# VC_Panning_Mixer_main.net
KiCad netlist of a schematic drawn in EAGLE
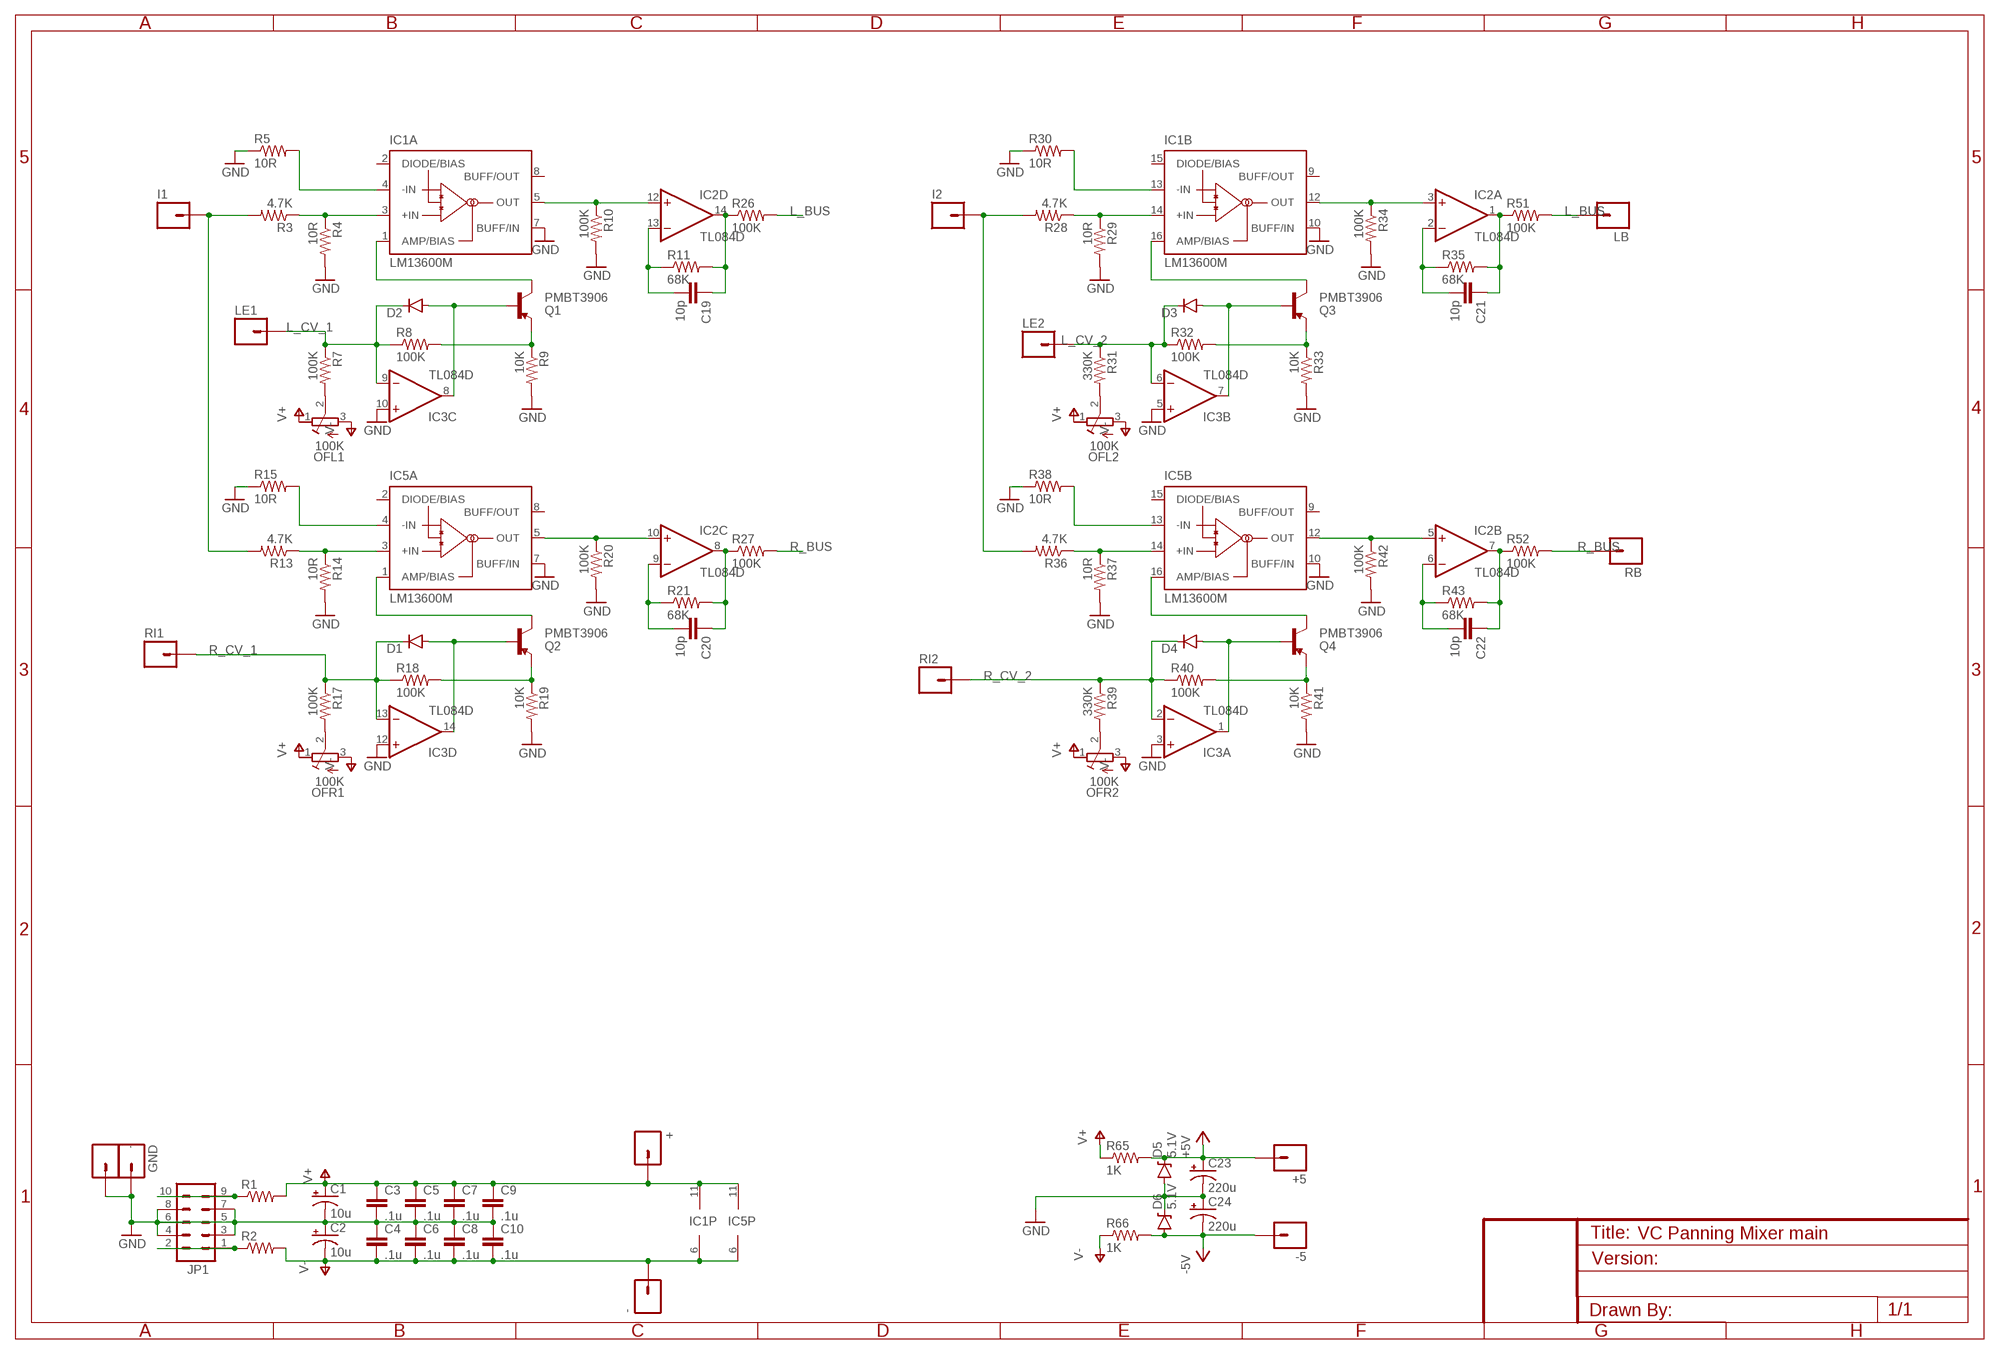
[diagram p0: schematic, sheet 1]

(export (version "E")
  (design (tool "Eeschema 10.0.6"))
  (components
    (comp (ref "+")
      (value "M01PTH")
      (footprint "eagle-import:1X01")
      (libsource (lib "eagle-import") (part "M01PTH"))
    )
    (comp (ref "+5")
      (value "M01PTH")
      (footprint "eagle-import:1X01")
      (libsource (lib "eagle-import") (part "M01PTH"))
    )
    (comp (ref "-")
      (value "M01PTH")
      (footprint "eagle-import:1X01")
      (libsource (lib "eagle-import") (part "M01PTH"))
    )
    (comp (ref "-5")
      (value "M01PTH")
      (footprint "eagle-import:1X01")
      (libsource (lib "eagle-import") (part "M01PTH"))
    )
    (comp (ref ".")
      (value "M01PTH")
      (footprint "eagle-import:1X01")
      (libsource (lib "eagle-import") (part "M01PTH"))
    )
    (comp (ref "C1")
      (value "10u")
      (footprint "eagle-import:CPOL-RADIAL-10UF-25V")
      (libsource (lib "eagle-import") (part "CAP_POLPTH2"))
    )
    (comp (ref "C2")
      (value "10u")
      (footprint "eagle-import:CPOL-RADIAL-10UF-25V")
      (libsource (lib "eagle-import") (part "CAP_POLPTH2"))
    )
    (comp (ref "C3")
      (value ".1u")
      (footprint "eagle-import:0805")
      (libsource (lib "eagle-import") (part "CAP0805"))
    )
    (comp (ref "C4")
      (value ".1u")
      (footprint "eagle-import:0805")
      (libsource (lib "eagle-import") (part "CAP0805"))
    )
    (comp (ref "C5")
      (value ".1u")
      (footprint "eagle-import:0805")
      (libsource (lib "eagle-import") (part "CAP0805"))
    )
    (comp (ref "C6")
      (value ".1u")
      (footprint "eagle-import:0805")
      (libsource (lib "eagle-import") (part "CAP0805"))
    )
    (comp (ref "C7")
      (value ".1u")
      (footprint "eagle-import:0805")
      (libsource (lib "eagle-import") (part "CAP0805"))
    )
    (comp (ref "C8")
      (value ".1u")
      (footprint "eagle-import:0805")
      (libsource (lib "eagle-import") (part "CAP0805"))
    )
    (comp (ref "C9")
      (value ".1u")
      (footprint "eagle-import:0805")
      (libsource (lib "eagle-import") (part "CAP0805"))
    )
    (comp (ref "C10")
      (value ".1u")
      (footprint "eagle-import:0805")
      (libsource (lib "eagle-import") (part "CAP0805"))
    )
    (comp (ref "C19")
      (value "10p")
      (footprint "eagle-import:0805")
      (libsource (lib "eagle-import") (part "CAP0805"))
    )
    (comp (ref "C20")
      (value "10p")
      (footprint "eagle-import:0805")
      (libsource (lib "eagle-import") (part "CAP0805"))
    )
    (comp (ref "C21")
      (value "10p")
      (footprint "eagle-import:0805")
      (libsource (lib "eagle-import") (part "CAP0805"))
    )
    (comp (ref "C22")
      (value "10p")
      (footprint "eagle-import:0805")
      (libsource (lib "eagle-import") (part "CAP0805"))
    )
    (comp (ref "C23")
      (value "220u")
      (footprint "eagle-import:CPOL-RADIAL-10UF-25V")
      (libsource (lib "eagle-import") (part "CAP_POLPTH2"))
    )
    (comp (ref "C24")
      (value "220u")
      (footprint "eagle-import:CPOL-RADIAL-10UF-25V")
      (libsource (lib "eagle-import") (part "CAP_POLPTH2"))
    )
    (comp (ref "D1")
      (value "DIODESOD123")
      (footprint "eagle-import:SOD-123")
      (libsource (lib "eagle-import") (part "DIODESOD123"))
    )
    (comp (ref "D2")
      (value "DIODESOD123")
      (footprint "eagle-import:SOD-123")
      (libsource (lib "eagle-import") (part "DIODESOD123"))
    )
    (comp (ref "D3")
      (value "DIODESOD123")
      (footprint "eagle-import:SOD-123")
      (libsource (lib "eagle-import") (part "DIODESOD123"))
    )
    (comp (ref "D4")
      (value "DIODESOD123")
      (footprint "eagle-import:SOD-123")
      (libsource (lib "eagle-import") (part "DIODESOD123"))
    )
    (comp (ref "D5")
      (value "5.1V")
      (footprint "eagle-import:SOD-123")
      (libsource (lib "eagle-import") (part "DIODE-ZENER16V"))
    )
    (comp (ref "D6")
      (value "5.1V")
      (footprint "eagle-import:SOD-123")
      (libsource (lib "eagle-import") (part "DIODE-ZENER16V"))
    )
    (comp (ref "GND")
      (value "M01PTH")
      (footprint "eagle-import:1X01")
      (libsource (lib "eagle-import") (part "M01PTH"))
    )
    (comp (ref "I1")
      (value "M01PTH")
      (footprint "eagle-import:1X01")
      (libsource (lib "eagle-import") (part "M01PTH"))
    )
    (comp (ref "I2")
      (value "M01PTH")
      (footprint "eagle-import:1X01")
      (libsource (lib "eagle-import") (part "M01PTH"))
    )
    (comp (ref "IC1")
      (value "LM13600M")
      (footprint "eagle-import:SO16")
      (libsource (lib "eagle-import") (part "LM13600M"))
    )
    (comp (ref "IC2")
      (value "TL084D")
      (footprint "eagle-import:SO14")
      (libsource (lib "eagle-import") (part "TL084D"))
    )
    (comp (ref "IC3")
      (value "TL084D")
      (footprint "eagle-import:SO14")
      (libsource (lib "eagle-import") (part "TL084D"))
    )
    (comp (ref "IC5")
      (value "LM13600M")
      (footprint "eagle-import:SO16")
      (libsource (lib "eagle-import") (part "LM13600M"))
    )
    (comp (ref "JP1")
      (value "M05X2PTH")
      (footprint "eagle-import:AVR_ICSP")
      (libsource (lib "eagle-import") (part "M05X2PTH"))
    )
    (comp (ref "LB")
      (value "M01PTH")
      (footprint "eagle-import:1X01")
      (libsource (lib "eagle-import") (part "M01PTH"))
    )
    (comp (ref "LE1")
      (value "M01PTH")
      (footprint "eagle-import:1X01")
      (libsource (lib "eagle-import") (part "M01PTH"))
    )
    (comp (ref "LE2")
      (value "M01PTH")
      (footprint "eagle-import:1X01")
      (libsource (lib "eagle-import") (part "M01PTH"))
    )
    (comp (ref "OFL1")
      (value "100K")
      (footprint "eagle-import:RTRIM3314G")
      (libsource (lib "eagle-import") (part "R-TRIMM3314G"))
    )
    (comp (ref "OFL2")
      (value "100K")
      (footprint "eagle-import:RTRIM3314G")
      (libsource (lib "eagle-import") (part "R-TRIMM3314G"))
    )
    (comp (ref "OFR1")
      (value "100K")
      (footprint "eagle-import:RTRIM3314G")
      (libsource (lib "eagle-import") (part "R-TRIMM3314G"))
    )
    (comp (ref "OFR2")
      (value "100K")
      (footprint "eagle-import:RTRIM3314G")
      (libsource (lib "eagle-import") (part "R-TRIMM3314G"))
    )
    (comp (ref "Q1")
      (value "PMBT3906")
      (footprint "eagle-import:SOT23-3")
      (libsource (lib "eagle-import") (part "TRANSISTOR_PNPPMBT3906"))
    )
    (comp (ref "Q2")
      (value "PMBT3906")
      (footprint "eagle-import:SOT23-3")
      (libsource (lib "eagle-import") (part "TRANSISTOR_PNPPMBT3906"))
    )
    (comp (ref "Q3")
      (value "PMBT3906")
      (footprint "eagle-import:SOT23-3")
      (libsource (lib "eagle-import") (part "TRANSISTOR_PNPPMBT3906"))
    )
    (comp (ref "Q4")
      (value "PMBT3906")
      (footprint "eagle-import:SOT23-3")
      (libsource (lib "eagle-import") (part "TRANSISTOR_PNPPMBT3906"))
    )
    (comp (ref "R1")
      (value "RESISTOR0805-RES")
      (footprint "eagle-import:0805@1")
      (libsource (lib "eagle-import") (part "RESISTOR0805-RES"))
    )
    (comp (ref "R2")
      (value "RESISTOR0805-RES")
      (footprint "eagle-import:0805@1")
      (libsource (lib "eagle-import") (part "RESISTOR0805-RES"))
    )
    (comp (ref "R3")
      (value "4.7K")
      (footprint "eagle-import:0805")
      (libsource (lib "eagle-import") (part "SparkFun-Resistors_RESISTOR0805-RES"))
    )
    (comp (ref "R4")
      (value "10R")
      (footprint "eagle-import:0805")
      (libsource (lib "eagle-import") (part "SparkFun-Resistors_RESISTOR0805-RES"))
    )
    (comp (ref "R5")
      (value "10R")
      (footprint "eagle-import:0805")
      (libsource (lib "eagle-import") (part "SparkFun-Resistors_RESISTOR0805-RES"))
    )
    (comp (ref "R7")
      (value "100K")
      (footprint "eagle-import:0805")
      (libsource (lib "eagle-import") (part "SparkFun-Resistors_RESISTOR0805-RES"))
    )
    (comp (ref "R8")
      (value "100K")
      (footprint "eagle-import:0805")
      (libsource (lib "eagle-import") (part "SparkFun-Resistors_RESISTOR0805-RES"))
    )
    (comp (ref "R9")
      (value "10K")
      (footprint "eagle-import:0805")
      (libsource (lib "eagle-import") (part "SparkFun-Resistors_RESISTOR0805-RES"))
    )
    (comp (ref "R10")
      (value "100K")
      (footprint "eagle-import:0805")
      (libsource (lib "eagle-import") (part "SparkFun-Resistors_RESISTOR0805-RES"))
    )
    (comp (ref "R11")
      (value "68K")
      (footprint "eagle-import:0805")
      (libsource (lib "eagle-import") (part "SparkFun-Resistors_RESISTOR0805-RES"))
    )
    (comp (ref "R13")
      (value "4.7K")
      (footprint "eagle-import:0805")
      (libsource (lib "eagle-import") (part "SparkFun-Resistors_RESISTOR0805-RES"))
    )
    (comp (ref "R14")
      (value "10R")
      (footprint "eagle-import:0805")
      (libsource (lib "eagle-import") (part "SparkFun-Resistors_RESISTOR0805-RES"))
    )
    (comp (ref "R15")
      (value "10R")
      (footprint "eagle-import:0805")
      (libsource (lib "eagle-import") (part "SparkFun-Resistors_RESISTOR0805-RES"))
    )
    (comp (ref "R17")
      (value "100K")
      (footprint "eagle-import:0805")
      (libsource (lib "eagle-import") (part "SparkFun-Resistors_RESISTOR0805-RES"))
    )
    (comp (ref "R18")
      (value "100K")
      (footprint "eagle-import:0805")
      (libsource (lib "eagle-import") (part "SparkFun-Resistors_RESISTOR0805-RES"))
    )
    (comp (ref "R19")
      (value "10K")
      (footprint "eagle-import:0805")
      (libsource (lib "eagle-import") (part "SparkFun-Resistors_RESISTOR0805-RES"))
    )
    (comp (ref "R20")
      (value "100K")
      (footprint "eagle-import:0805")
      (libsource (lib "eagle-import") (part "SparkFun-Resistors_RESISTOR0805-RES"))
    )
    (comp (ref "R21")
      (value "68K")
      (footprint "eagle-import:0805")
      (libsource (lib "eagle-import") (part "SparkFun-Resistors_RESISTOR0805-RES"))
    )
    (comp (ref "R26")
      (value "100K")
      (footprint "eagle-import:0805")
      (libsource (lib "eagle-import") (part "SparkFun-Resistors_RESISTOR0805-RES"))
    )
    (comp (ref "R27")
      (value "100K")
      (footprint "eagle-import:0805")
      (libsource (lib "eagle-import") (part "SparkFun-Resistors_RESISTOR0805-RES"))
    )
    (comp (ref "R28")
      (value "4.7K")
      (footprint "eagle-import:0805")
      (libsource (lib "eagle-import") (part "SparkFun-Resistors_RESISTOR0805-RES"))
    )
    (comp (ref "R29")
      (value "10R")
      (footprint "eagle-import:0805")
      (libsource (lib "eagle-import") (part "SparkFun-Resistors_RESISTOR0805-RES"))
    )
    (comp (ref "R30")
      (value "10R")
      (footprint "eagle-import:0805")
      (libsource (lib "eagle-import") (part "SparkFun-Resistors_RESISTOR0805-RES"))
    )
    (comp (ref "R31")
      (value "330K")
      (footprint "eagle-import:0805")
      (libsource (lib "eagle-import") (part "SparkFun-Resistors_RESISTOR0805-RES"))
    )
    (comp (ref "R32")
      (value "100K")
      (footprint "eagle-import:0805")
      (libsource (lib "eagle-import") (part "SparkFun-Resistors_RESISTOR0805-RES"))
    )
    (comp (ref "R33")
      (value "10K")
      (footprint "eagle-import:0805")
      (libsource (lib "eagle-import") (part "SparkFun-Resistors_RESISTOR0805-RES"))
    )
    (comp (ref "R34")
      (value "100K")
      (footprint "eagle-import:0805")
      (libsource (lib "eagle-import") (part "SparkFun-Resistors_RESISTOR0805-RES"))
    )
    (comp (ref "R35")
      (value "68K")
      (footprint "eagle-import:0805")
      (libsource (lib "eagle-import") (part "SparkFun-Resistors_RESISTOR0805-RES"))
    )
    (comp (ref "R36")
      (value "4.7K")
      (footprint "eagle-import:0805")
      (libsource (lib "eagle-import") (part "SparkFun-Resistors_RESISTOR0805-RES"))
    )
    (comp (ref "R37")
      (value "10R")
      (footprint "eagle-import:0805")
      (libsource (lib "eagle-import") (part "SparkFun-Resistors_RESISTOR0805-RES"))
    )
    (comp (ref "R38")
      (value "10R")
      (footprint "eagle-import:0805")
      (libsource (lib "eagle-import") (part "SparkFun-Resistors_RESISTOR0805-RES"))
    )
    (comp (ref "R39")
      (value "330K")
      (footprint "eagle-import:0805")
      (libsource (lib "eagle-import") (part "SparkFun-Resistors_RESISTOR0805-RES"))
    )
    (comp (ref "R40")
      (value "100K")
      (footprint "eagle-import:0805")
      (libsource (lib "eagle-import") (part "SparkFun-Resistors_RESISTOR0805-RES"))
    )
    (comp (ref "R41")
      (value "10K")
      (footprint "eagle-import:0805")
      (libsource (lib "eagle-import") (part "SparkFun-Resistors_RESISTOR0805-RES"))
    )
    (comp (ref "R42")
      (value "100K")
      (footprint "eagle-import:0805")
      (libsource (lib "eagle-import") (part "SparkFun-Resistors_RESISTOR0805-RES"))
    )
    (comp (ref "R43")
      (value "68K")
      (footprint "eagle-import:0805")
      (libsource (lib "eagle-import") (part "SparkFun-Resistors_RESISTOR0805-RES"))
    )
    (comp (ref "R51")
      (value "100K")
      (footprint "eagle-import:0805")
      (libsource (lib "eagle-import") (part "SparkFun-Resistors_RESISTOR0805-RES"))
    )
    (comp (ref "R52")
      (value "100K")
      (footprint "eagle-import:0805")
      (libsource (lib "eagle-import") (part "SparkFun-Resistors_RESISTOR0805-RES"))
    )
    (comp (ref "R65")
      (value "1K")
      (footprint "eagle-import:0805")
      (libsource (lib "eagle-import") (part "SparkFun-Resistors_RESISTOR0805-RES"))
    )
    (comp (ref "R66")
      (value "1K")
      (footprint "eagle-import:0805")
      (libsource (lib "eagle-import") (part "SparkFun-Resistors_RESISTOR0805-RES"))
    )
    (comp (ref "RB")
      (value "M01PTH")
      (footprint "eagle-import:1X01")
      (libsource (lib "eagle-import") (part "M01PTH"))
    )
    (comp (ref "RI1")
      (value "M01PTH")
      (footprint "eagle-import:1X01")
      (libsource (lib "eagle-import") (part "M01PTH"))
    )
    (comp (ref "RI2")
      (value "M01PTH")
      (footprint "eagle-import:1X01")
      (libsource (lib "eagle-import") (part "M01PTH"))
    )
  )
  (nets
    (net (code "1") (name "+5V") (class "Default")
      (node (ref "+5") (pin "1") (pinfunction "1_1") (pintype "passive"))
      (node (ref "C23") (pin "1") (pinfunction "+_1") (pintype "passive"))
      (node (ref "D5") (pin "C") (pinfunction "C_C") (pintype "passive"))
      (node (ref "R65") (pin "2") (pinfunction "2_2") (pintype "passive"))
    )
    (net (code "2") (name "-5V") (class "Default")
      (node (ref "-5") (pin "1") (pinfunction "1_1") (pintype "passive"))
      (node (ref "C24") (pin "2") (pinfunction "-_2") (pintype "passive"))
      (node (ref "D6") (pin "A") (pinfunction "A_A") (pintype "passive"))
      (node (ref "R66") (pin "2") (pinfunction "2_2") (pintype "passive"))
    )
    (net (code "3") (name "/L_BUS") (class "Default")
      (node (ref "LB") (pin "1") (pinfunction "1_1") (pintype "passive"))
      (node (ref "R26") (pin "2") (pinfunction "2_2") (pintype "passive"))
      (node (ref "R51") (pin "2") (pinfunction "2_2") (pintype "passive"))
    )
    (net (code "4") (name "/L_CV_1") (class "Default")
      (node (ref "D2") (pin "C") (pinfunction "C_C") (pintype "passive"))
      (node (ref "IC3") (pin "9") (pinfunction "-IN_9") (pintype "input"))
      (node (ref "LE1") (pin "1") (pinfunction "1_1") (pintype "passive"))
      (node (ref "R7") (pin "1") (pinfunction "1_1") (pintype "passive"))
      (node (ref "R8") (pin "1") (pinfunction "1_1") (pintype "passive"))
    )
    (net (code "5") (name "/L_CV_2") (class "Default")
      (node (ref "D3") (pin "C") (pinfunction "C_C") (pintype "passive"))
      (node (ref "IC3") (pin "6") (pinfunction "-IN_6") (pintype "input"))
      (node (ref "LE2") (pin "1") (pinfunction "1_1") (pintype "passive"))
      (node (ref "R31") (pin "1") (pinfunction "1_1") (pintype "passive"))
      (node (ref "R32") (pin "1") (pinfunction "1_1") (pintype "passive"))
    )
    (net (code "6") (name "/R_BUS") (class "Default")
      (node (ref "R27") (pin "2") (pinfunction "2_2") (pintype "passive"))
      (node (ref "R52") (pin "2") (pinfunction "2_2") (pintype "passive"))
      (node (ref "RB") (pin "1") (pinfunction "1_1") (pintype "passive"))
    )
    (net (code "7") (name "/R_CV_1") (class "Default")
      (node (ref "D1") (pin "C") (pinfunction "C_C") (pintype "passive"))
      (node (ref "IC3") (pin "13") (pinfunction "-IN_13") (pintype "input"))
      (node (ref "R17") (pin "1") (pinfunction "1_1") (pintype "passive"))
      (node (ref "R18") (pin "1") (pinfunction "1_1") (pintype "passive"))
      (node (ref "RI1") (pin "1") (pinfunction "1_1") (pintype "passive"))
    )
    (net (code "8") (name "/R_CV_2") (class "Default")
      (node (ref "D4") (pin "C") (pinfunction "C_C") (pintype "passive"))
      (node (ref "IC3") (pin "2") (pinfunction "-IN_2") (pintype "input"))
      (node (ref "R39") (pin "1") (pinfunction "1_1") (pintype "passive"))
      (node (ref "R40") (pin "1") (pinfunction "1_1") (pintype "passive"))
      (node (ref "RI2") (pin "1") (pinfunction "1_1") (pintype "passive"))
    )
    (net (code "9") (name "GND") (class "Default")
      (node (ref ".") (pin "1") (pinfunction "1_1") (pintype "passive"))
      (node (ref "C1") (pin "2") (pinfunction "-_2") (pintype "passive"))
      (node (ref "C10") (pin "1") (pinfunction "1_1") (pintype "passive"))
      (node (ref "C2") (pin "1") (pinfunction "+_1") (pintype "passive"))
      (node (ref "C23") (pin "2") (pinfunction "-_2") (pintype "passive"))
      (node (ref "C24") (pin "1") (pinfunction "+_1") (pintype "passive"))
      (node (ref "C3") (pin "2") (pinfunction "2_2") (pintype "passive"))
      (node (ref "C4") (pin "1") (pinfunction "1_1") (pintype "passive"))
      (node (ref "C5") (pin "2") (pinfunction "2_2") (pintype "passive"))
      (node (ref "C6") (pin "1") (pinfunction "1_1") (pintype "passive"))
      (node (ref "C7") (pin "2") (pinfunction "2_2") (pintype "passive"))
      (node (ref "C8") (pin "1") (pinfunction "1_1") (pintype "passive"))
      (node (ref "C9") (pin "2") (pinfunction "2_2") (pintype "passive"))
      (node (ref "D5") (pin "A") (pinfunction "A_A") (pintype "passive"))
      (node (ref "D6") (pin "C") (pinfunction "C_C") (pintype "passive"))
      (node (ref "GND") (pin "1") (pinfunction "1_1") (pintype "passive"))
      (node (ref "IC1") (pin "10") (pinfunction "BUFF/IN_10") (pintype "input"))
      (node (ref "IC1") (pin "7") (pinfunction "BUFF/IN_7") (pintype "input"))
      (node (ref "IC3") (pin "10") (pinfunction "+IN_10") (pintype "input"))
      (node (ref "IC3") (pin "12") (pinfunction "+IN_12") (pintype "input"))
      (node (ref "IC3") (pin "3") (pinfunction "+IN_3") (pintype "input"))
      (node (ref "IC3") (pin "5") (pinfunction "+IN_5") (pintype "input"))
      (node (ref "IC5") (pin "10") (pinfunction "BUFF/IN_10") (pintype "input"))
      (node (ref "IC5") (pin "7") (pinfunction "BUFF/IN_7") (pintype "input"))
      (node (ref "JP1") (pin "3") (pinfunction "3_3") (pintype "passive"))
      (node (ref "JP1") (pin "4") (pinfunction "4_4") (pintype "passive"))
      (node (ref "JP1") (pin "5") (pinfunction "5_5") (pintype "passive"))
      (node (ref "JP1") (pin "6") (pinfunction "6_6") (pintype "passive"))
      (node (ref "JP1") (pin "7") (pinfunction "7_7") (pintype "passive"))
      (node (ref "JP1") (pin "8") (pinfunction "8_8") (pintype "passive"))
      (node (ref "R10") (pin "2") (pinfunction "2_2") (pintype "passive"))
      (node (ref "R14") (pin "2") (pinfunction "2_2") (pintype "passive"))
      (node (ref "R15") (pin "1") (pinfunction "1_1") (pintype "passive"))
      (node (ref "R19") (pin "2") (pinfunction "2_2") (pintype "passive"))
      (node (ref "R20") (pin "2") (pinfunction "2_2") (pintype "passive"))
      (node (ref "R29") (pin "2") (pinfunction "2_2") (pintype "passive"))
      (node (ref "R30") (pin "1") (pinfunction "1_1") (pintype "passive"))
      (node (ref "R33") (pin "2") (pinfunction "2_2") (pintype "passive"))
      (node (ref "R34") (pin "2") (pinfunction "2_2") (pintype "passive"))
      (node (ref "R37") (pin "2") (pinfunction "2_2") (pintype "passive"))
      (node (ref "R38") (pin "1") (pinfunction "1_1") (pintype "passive"))
      (node (ref "R4") (pin "2") (pinfunction "2_2") (pintype "passive"))
      (node (ref "R41") (pin "2") (pinfunction "2_2") (pintype "passive"))
      (node (ref "R42") (pin "2") (pinfunction "2_2") (pintype "passive"))
      (node (ref "R5") (pin "1") (pinfunction "1_1") (pintype "passive"))
      (node (ref "R9") (pin "2") (pinfunction "2_2") (pintype "passive"))
    )
    (net (code "10") (name "Net-(I1-Pad1)") (class "Default")
      (node (ref "I1") (pin "1") (pinfunction "1_1") (pintype "passive"))
      (node (ref "R13") (pin "2") (pinfunction "2_2") (pintype "passive"))
      (node (ref "R3") (pin "2") (pinfunction "2_2") (pintype "passive"))
    )
    (net (code "11") (name "Net-(I2-Pad1)") (class "Default")
      (node (ref "I2") (pin "1") (pinfunction "1_1") (pintype "passive"))
      (node (ref "R28") (pin "2") (pinfunction "2_2") (pintype "passive"))
      (node (ref "R36") (pin "2") (pinfunction "2_2") (pintype "passive"))
    )
    (net (code "12") (name "Net-(IC1A-+IN)") (class "Default")
      (node (ref "IC1") (pin "3") (pinfunction "+IN_3") (pintype "input"))
      (node (ref "R3") (pin "1") (pinfunction "1_1") (pintype "passive"))
      (node (ref "R4") (pin "1") (pinfunction "1_1") (pintype "passive"))
    )
    (net (code "13") (name "Net-(IC1A--IN)") (class "Default")
      (node (ref "IC1") (pin "4") (pinfunction "-IN_4") (pintype "input"))
      (node (ref "R5") (pin "2") (pinfunction "2_2") (pintype "passive"))
    )
    (net (code "14") (name "Net-(IC1A-AMP{slash}BIAS)") (class "Default")
      (node (ref "IC1") (pin "1") (pinfunction "AMP/BIAS_1") (pintype "passive"))
      (node (ref "Q1") (pin "3") (pinfunction "C_3") (pintype "passive"))
    )
    (net (code "15") (name "Net-(IC1A-OUT)") (class "Default")
      (node (ref "IC1") (pin "5") (pinfunction "OUT_5") (pintype "output"))
      (node (ref "IC2") (pin "12") (pinfunction "+IN_12") (pintype "input"))
      (node (ref "R10") (pin "1") (pinfunction "1_1") (pintype "passive"))
    )
    (net (code "16") (name "Net-(IC1B-+IN)") (class "Default")
      (node (ref "IC1") (pin "14") (pinfunction "+IN_14") (pintype "input"))
      (node (ref "R28") (pin "1") (pinfunction "1_1") (pintype "passive"))
      (node (ref "R29") (pin "1") (pinfunction "1_1") (pintype "passive"))
    )
    (net (code "17") (name "Net-(IC1B--IN)") (class "Default")
      (node (ref "IC1") (pin "13") (pinfunction "-IN_13") (pintype "input"))
      (node (ref "R30") (pin "2") (pinfunction "2_2") (pintype "passive"))
    )
    (net (code "18") (name "Net-(IC1B-AMP{slash}BIAS)") (class "Default")
      (node (ref "IC1") (pin "16") (pinfunction "AMP/BIAS_16") (pintype "passive"))
      (node (ref "Q3") (pin "3") (pinfunction "C_3") (pintype "passive"))
    )
    (net (code "19") (name "Net-(IC1B-OUT)") (class "Default")
      (node (ref "IC1") (pin "12") (pinfunction "OUT_12") (pintype "output"))
      (node (ref "IC2") (pin "3") (pinfunction "+IN_3") (pintype "input"))
      (node (ref "R34") (pin "1") (pinfunction "1_1") (pintype "passive"))
    )
    (net (code "20") (name "Net-(IC2A--IN)") (class "Default")
      (node (ref "C21") (pin "2") (pinfunction "2_2") (pintype "passive"))
      (node (ref "IC2") (pin "2") (pinfunction "-IN_2") (pintype "input"))
      (node (ref "R35") (pin "1") (pinfunction "1_1") (pintype "passive"))
    )
    (net (code "21") (name "Net-(IC2A-OUT)") (class "Default")
      (node (ref "C21") (pin "1") (pinfunction "1_1") (pintype "passive"))
      (node (ref "IC2") (pin "1") (pinfunction "OUT_1") (pintype "output"))
      (node (ref "R35") (pin "2") (pinfunction "2_2") (pintype "passive"))
      (node (ref "R51") (pin "1") (pinfunction "1_1") (pintype "passive"))
    )
    (net (code "22") (name "Net-(IC2B-+IN)") (class "Default")
      (node (ref "IC2") (pin "5") (pinfunction "+IN_5") (pintype "input"))
      (node (ref "IC5") (pin "12") (pinfunction "OUT_12") (pintype "output"))
      (node (ref "R42") (pin "1") (pinfunction "1_1") (pintype "passive"))
    )
    (net (code "23") (name "Net-(IC2B--IN)") (class "Default")
      (node (ref "C22") (pin "2") (pinfunction "2_2") (pintype "passive"))
      (node (ref "IC2") (pin "6") (pinfunction "-IN_6") (pintype "input"))
      (node (ref "R43") (pin "1") (pinfunction "1_1") (pintype "passive"))
    )
    (net (code "24") (name "Net-(IC2B-OUT)") (class "Default")
      (node (ref "C22") (pin "1") (pinfunction "1_1") (pintype "passive"))
      (node (ref "IC2") (pin "7") (pinfunction "OUT_7") (pintype "output"))
      (node (ref "R43") (pin "2") (pinfunction "2_2") (pintype "passive"))
      (node (ref "R52") (pin "1") (pinfunction "1_1") (pintype "passive"))
    )
    (net (code "25") (name "Net-(IC2C-+IN)") (class "Default")
      (node (ref "IC2") (pin "10") (pinfunction "+IN_10") (pintype "input"))
      (node (ref "IC5") (pin "5") (pinfunction "OUT_5") (pintype "output"))
      (node (ref "R20") (pin "1") (pinfunction "1_1") (pintype "passive"))
    )
    (net (code "26") (name "Net-(IC2C--IN)") (class "Default")
      (node (ref "C20") (pin "2") (pinfunction "2_2") (pintype "passive"))
      (node (ref "IC2") (pin "9") (pinfunction "-IN_9") (pintype "input"))
      (node (ref "R21") (pin "1") (pinfunction "1_1") (pintype "passive"))
    )
    (net (code "27") (name "Net-(IC2C-OUT)") (class "Default")
      (node (ref "C20") (pin "1") (pinfunction "1_1") (pintype "passive"))
      (node (ref "IC2") (pin "8") (pinfunction "OUT_8") (pintype "output"))
      (node (ref "R21") (pin "2") (pinfunction "2_2") (pintype "passive"))
      (node (ref "R27") (pin "1") (pinfunction "1_1") (pintype "passive"))
    )
    (net (code "28") (name "Net-(IC2D--IN)") (class "Default")
      (node (ref "C19") (pin "2") (pinfunction "2_2") (pintype "passive"))
      (node (ref "IC2") (pin "13") (pinfunction "-IN_13") (pintype "input"))
      (node (ref "R11") (pin "1") (pinfunction "1_1") (pintype "passive"))
    )
    (net (code "29") (name "Net-(IC2D-OUT)") (class "Default")
      (node (ref "C19") (pin "1") (pinfunction "1_1") (pintype "passive"))
      (node (ref "IC2") (pin "14") (pinfunction "OUT_14") (pintype "output"))
      (node (ref "R11") (pin "2") (pinfunction "2_2") (pintype "passive"))
      (node (ref "R26") (pin "1") (pinfunction "1_1") (pintype "passive"))
    )
    (net (code "30") (name "Net-(IC3A-OUT)") (class "Default")
      (node (ref "D4") (pin "A") (pinfunction "A_A") (pintype "passive"))
      (node (ref "IC3") (pin "1") (pinfunction "OUT_1") (pintype "output"))
      (node (ref "Q4") (pin "1") (pinfunction "B_1") (pintype "passive"))
    )
    (net (code "31") (name "Net-(IC3B-OUT)") (class "Default")
      (node (ref "D3") (pin "A") (pinfunction "A_A") (pintype "passive"))
      (node (ref "IC3") (pin "7") (pinfunction "OUT_7") (pintype "output"))
      (node (ref "Q3") (pin "1") (pinfunction "B_1") (pintype "passive"))
    )
    (net (code "32") (name "Net-(IC3C-OUT)") (class "Default")
      (node (ref "D2") (pin "A") (pinfunction "A_A") (pintype "passive"))
      (node (ref "IC3") (pin "8") (pinfunction "OUT_8") (pintype "output"))
      (node (ref "Q1") (pin "1") (pinfunction "B_1") (pintype "passive"))
    )
    (net (code "33") (name "Net-(IC3D-OUT)") (class "Default")
      (node (ref "D1") (pin "A") (pinfunction "A_A") (pintype "passive"))
      (node (ref "IC3") (pin "14") (pinfunction "OUT_14") (pintype "output"))
      (node (ref "Q2") (pin "1") (pinfunction "B_1") (pintype "passive"))
    )
    (net (code "34") (name "Net-(IC5A-+IN)") (class "Default")
      (node (ref "IC5") (pin "3") (pinfunction "+IN_3") (pintype "input"))
      (node (ref "R13") (pin "1") (pinfunction "1_1") (pintype "passive"))
      (node (ref "R14") (pin "1") (pinfunction "1_1") (pintype "passive"))
    )
    (net (code "35") (name "Net-(IC5A--IN)") (class "Default")
      (node (ref "IC5") (pin "4") (pinfunction "-IN_4") (pintype "input"))
      (node (ref "R15") (pin "2") (pinfunction "2_2") (pintype "passive"))
    )
    (net (code "36") (name "Net-(IC5A-AMP{slash}BIAS)") (class "Default")
      (node (ref "IC5") (pin "1") (pinfunction "AMP/BIAS_1") (pintype "passive"))
      (node (ref "Q2") (pin "3") (pinfunction "C_3") (pintype "passive"))
    )
    (net (code "37") (name "Net-(IC5B-+IN)") (class "Default")
      (node (ref "IC5") (pin "14") (pinfunction "+IN_14") (pintype "input"))
      (node (ref "R36") (pin "1") (pinfunction "1_1") (pintype "passive"))
      (node (ref "R37") (pin "1") (pinfunction "1_1") (pintype "passive"))
    )
    (net (code "38") (name "Net-(IC5B--IN)") (class "Default")
      (node (ref "IC5") (pin "13") (pinfunction "-IN_13") (pintype "input"))
      (node (ref "R38") (pin "2") (pinfunction "2_2") (pintype "passive"))
    )
    (net (code "39") (name "Net-(IC5B-AMP{slash}BIAS)") (class "Default")
      (node (ref "IC5") (pin "16") (pinfunction "AMP/BIAS_16") (pintype "passive"))
      (node (ref "Q4") (pin "3") (pinfunction "C_3") (pintype "passive"))
    )
    (net (code "40") (name "Net-(JP1-Pad1)") (class "Default")
      (node (ref "JP1") (pin "1") (pinfunction "1_1") (pintype "passive"))
      (node (ref "JP1") (pin "2") (pinfunction "2_2") (pintype "passive"))
      (node (ref "R2") (pin "1") (pinfunction "1_1") (pintype "passive"))
    )
    (net (code "41") (name "Net-(JP1-Pad10)") (class "Default")
      (node (ref "JP1") (pin "10") (pinfunction "10_10") (pintype "passive"))
      (node (ref "JP1") (pin "9") (pinfunction "9_9") (pintype "passive"))
      (node (ref "R1") (pin "1") (pinfunction "1_1") (pintype "passive"))
    )
    (net (code "42") (name "Net-(OFL1-S)") (class "Default")
      (node (ref "OFL1") (pin "2") (pinfunction "S_2") (pintype "passive"))
      (node (ref "R7") (pin "2") (pinfunction "2_2") (pintype "passive"))
    )
    (net (code "43") (name "Net-(OFL2-S)") (class "Default")
      (node (ref "OFL2") (pin "2") (pinfunction "S_2") (pintype "passive"))
      (node (ref "R31") (pin "2") (pinfunction "2_2") (pintype "passive"))
    )
    (net (code "44") (name "Net-(OFR1-S)") (class "Default")
      (node (ref "OFR1") (pin "2") (pinfunction "S_2") (pintype "passive"))
      (node (ref "R17") (pin "2") (pinfunction "2_2") (pintype "passive"))
    )
    (net (code "45") (name "Net-(OFR2-S)") (class "Default")
      (node (ref "OFR2") (pin "2") (pinfunction "S_2") (pintype "passive"))
      (node (ref "R39") (pin "2") (pinfunction "2_2") (pintype "passive"))
    )
    (net (code "46") (name "Net-(Q1-E)") (class "Default")
      (node (ref "Q1") (pin "2") (pinfunction "E_2") (pintype "passive"))
      (node (ref "R8") (pin "2") (pinfunction "2_2") (pintype "passive"))
      (node (ref "R9") (pin "1") (pinfunction "1_1") (pintype "passive"))
    )
    (net (code "47") (name "Net-(Q2-E)") (class "Default")
      (node (ref "Q2") (pin "2") (pinfunction "E_2") (pintype "passive"))
      (node (ref "R18") (pin "2") (pinfunction "2_2") (pintype "passive"))
      (node (ref "R19") (pin "1") (pinfunction "1_1") (pintype "passive"))
    )
    (net (code "48") (name "Net-(Q3-E)") (class "Default")
      (node (ref "Q3") (pin "2") (pinfunction "E_2") (pintype "passive"))
      (node (ref "R32") (pin "2") (pinfunction "2_2") (pintype "passive"))
      (node (ref "R33") (pin "1") (pinfunction "1_1") (pintype "passive"))
    )
    (net (code "49") (name "Net-(Q4-E)") (class "Default")
      (node (ref "Q4") (pin "2") (pinfunction "E_2") (pintype "passive"))
      (node (ref "R40") (pin "2") (pinfunction "2_2") (pintype "passive"))
      (node (ref "R41") (pin "1") (pinfunction "1_1") (pintype "passive"))
    )
    (net (code "50") (name "V+") (class "Default")
      (node (ref "+") (pin "1") (pinfunction "1_1") (pintype "passive"))
      (node (ref "C1") (pin "1") (pinfunction "+_1") (pintype "passive"))
      (node (ref "C3") (pin "1") (pinfunction "1_1") (pintype "passive"))
      (node (ref "C5") (pin "1") (pinfunction "1_1") (pintype "passive"))
      (node (ref "C7") (pin "1") (pinfunction "1_1") (pintype "passive"))
      (node (ref "C9") (pin "1") (pinfunction "1_1") (pintype "passive"))
      (node (ref "IC1") (pin "11") (pinfunction "V+_11") (pintype "power_in"))
      (node (ref "IC5") (pin "11") (pinfunction "V+_11") (pintype "power_in"))
      (node (ref "OFL1") (pin "1") (pinfunction "E_1") (pintype "passive"))
      (node (ref "OFL2") (pin "1") (pinfunction "E_1") (pintype "passive"))
      (node (ref "OFR1") (pin "1") (pinfunction "E_1") (pintype "passive"))
      (node (ref "OFR2") (pin "1") (pinfunction "E_1") (pintype "passive"))
      (node (ref "R1") (pin "2") (pinfunction "2_2") (pintype "passive"))
      (node (ref "R65") (pin "1") (pinfunction "1_1") (pintype "passive"))
    )
    (net (code "51") (name "V-") (class "Default")
      (node (ref "-") (pin "1") (pinfunction "1_1") (pintype "passive"))
      (node (ref "C10") (pin "2") (pinfunction "2_2") (pintype "passive"))
      (node (ref "C2") (pin "2") (pinfunction "-_2") (pintype "passive"))
      (node (ref "C4") (pin "2") (pinfunction "2_2") (pintype "passive"))
      (node (ref "C6") (pin "2") (pinfunction "2_2") (pintype "passive"))
      (node (ref "C8") (pin "2") (pinfunction "2_2") (pintype "passive"))
      (node (ref "IC1") (pin "6") (pinfunction "V-_6") (pintype "power_in"))
      (node (ref "IC5") (pin "6") (pinfunction "V-_6") (pintype "power_in"))
      (node (ref "OFL1") (pin "3") (pinfunction "A_3") (pintype "passive"))
      (node (ref "OFL2") (pin "3") (pinfunction "A_3") (pintype "passive"))
      (node (ref "OFR1") (pin "3") (pinfunction "A_3") (pintype "passive"))
      (node (ref "OFR2") (pin "3") (pinfunction "A_3") (pintype "passive"))
      (node (ref "R2") (pin "2") (pinfunction "2_2") (pintype "passive"))
      (node (ref "R66") (pin "1") (pinfunction "1_1") (pintype "passive"))
    )
    (net (code "52") (name "unconnected-(IC1A-BUFF{slash}OUT-Pad8)") (class "Default")
      (node (ref "IC1") (pin "8") (pinfunction "BUFF/OUT_8") (pintype "output"))
    )
    (net (code "53") (name "unconnected-(IC1A-DIODE{slash}BIAS-Pad2)") (class "Default")
      (node (ref "IC1") (pin "2") (pinfunction "DIODE/BIAS_2") (pintype "passive"))
    )
    (net (code "54") (name "unconnected-(IC1B-BUFF{slash}OUT-Pad9)") (class "Default")
      (node (ref "IC1") (pin "9") (pinfunction "BUFF/OUT_9") (pintype "output"))
    )
    (net (code "55") (name "unconnected-(IC1B-DIODE{slash}BIAS-Pad15)") (class "Default")
      (node (ref "IC1") (pin "15") (pinfunction "DIODE/BIAS_15") (pintype "passive"))
    )
    (net (code "56") (name "unconnected-(IC5A-BUFF{slash}OUT-Pad8)") (class "Default")
      (node (ref "IC5") (pin "8") (pinfunction "BUFF/OUT_8") (pintype "output"))
    )
    (net (code "57") (name "unconnected-(IC5A-DIODE{slash}BIAS-Pad2)") (class "Default")
      (node (ref "IC5") (pin "2") (pinfunction "DIODE/BIAS_2") (pintype "passive"))
    )
    (net (code "58") (name "unconnected-(IC5B-BUFF{slash}OUT-Pad9)") (class "Default")
      (node (ref "IC5") (pin "9") (pinfunction "BUFF/OUT_9") (pintype "output"))
    )
    (net (code "59") (name "unconnected-(IC5B-DIODE{slash}BIAS-Pad15)") (class "Default")
      (node (ref "IC5") (pin "15") (pinfunction "DIODE/BIAS_15") (pintype "passive"))
    )
  )
)
